# RF_EtherCard_Maniac.net
KiCad netlist of a schematic drawn in EAGLE
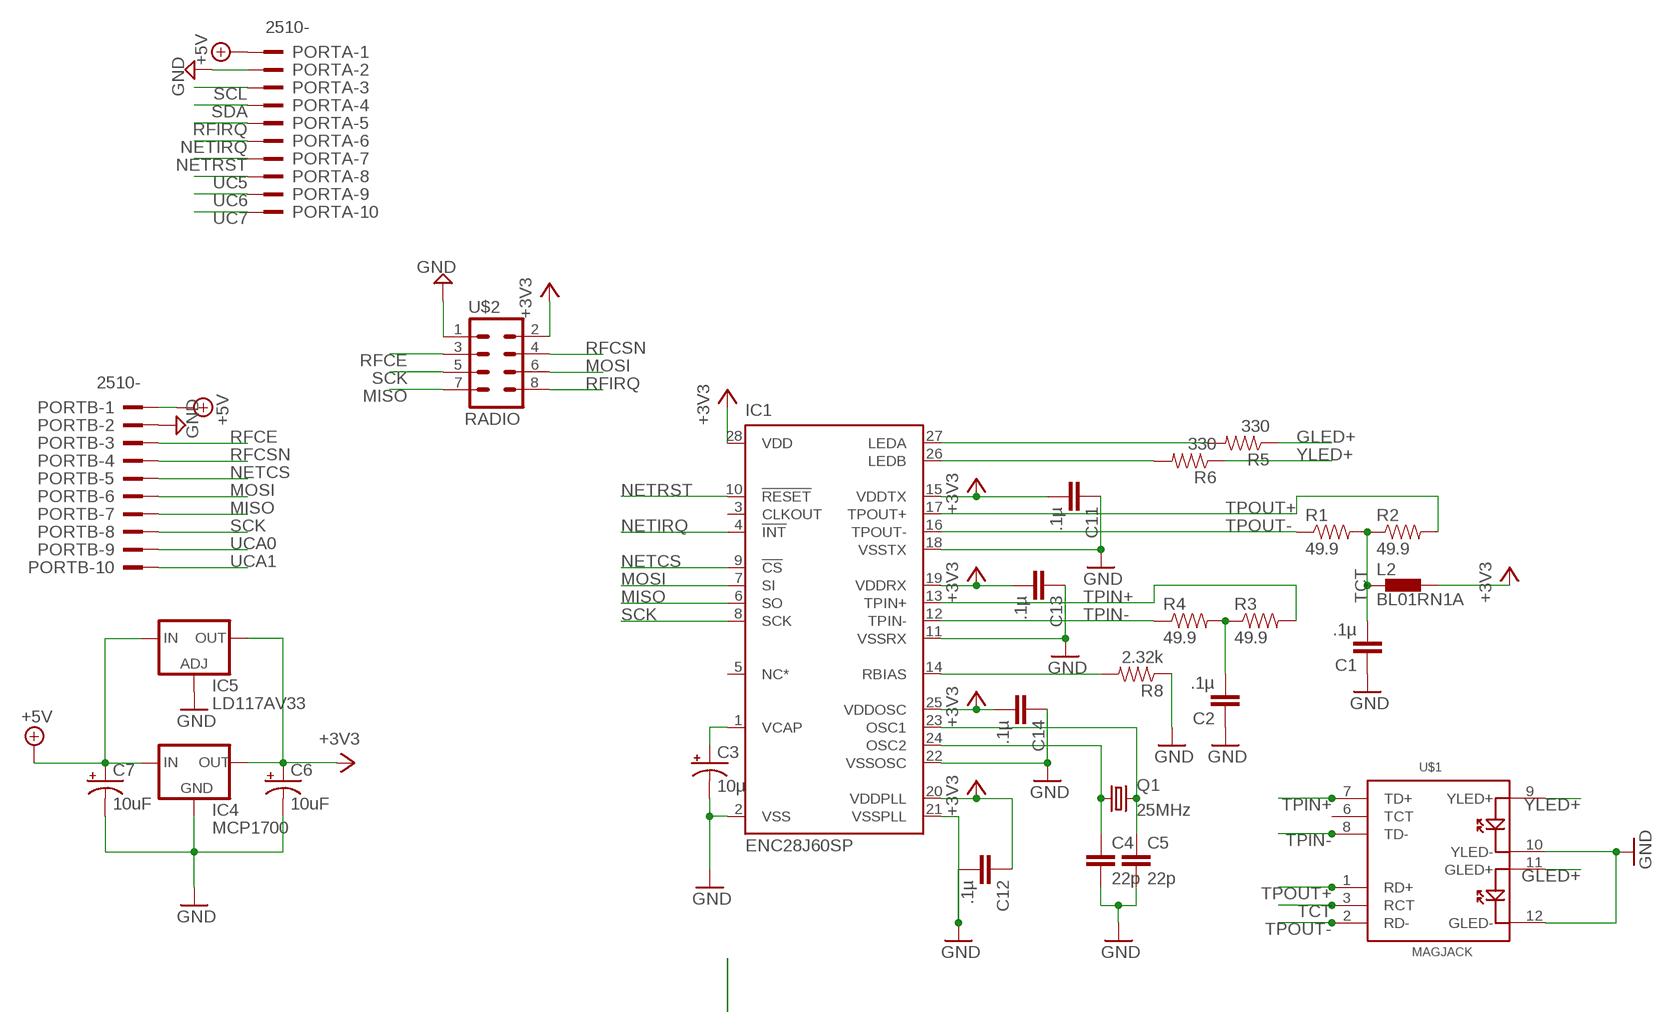
[diagram p0: schematic, sheet 1]

(export (version "E")
  (design (tool "Eeschema 10.0.6"))
  (components
    (comp (ref "C1")
      (value ".1µ")
      (footprint "eagle-import:CAP-PTH-SMALL")
      (libsource (lib "eagle-import") (part "CAPPTH"))
    )
    (comp (ref "C2")
      (value ".1µ")
      (footprint "eagle-import:CAP-PTH-SMALL")
      (libsource (lib "eagle-import") (part "CAPPTH"))
    )
    (comp (ref "C3")
      (value "10µ")
      (footprint "eagle-import:CPOL-RADIAL-10UF-25V")
      (libsource (lib "eagle-import") (part "CAP_POLPTH2"))
    )
    (comp (ref "C4")
      (value "22p")
      (footprint "eagle-import:CAP-PTH-SMALL")
      (libsource (lib "eagle-import") (part "CAPPTH"))
    )
    (comp (ref "C5")
      (value "22p")
      (footprint "eagle-import:CAP-PTH-SMALL")
      (libsource (lib "eagle-import") (part "CAPPTH"))
    )
    (comp (ref "C6")
      (value "10uF")
      (footprint "eagle-import:CPOL-RADIAL-10UF-25V")
      (libsource (lib "eagle-import") (part "CAP_POLPTH2"))
    )
    (comp (ref "C7")
      (value "10uF")
      (footprint "eagle-import:CPOL-RADIAL-10UF-25V")
      (libsource (lib "eagle-import") (part "CAP_POLPTH2"))
    )
    (comp (ref "C11")
      (value ".1µ")
      (footprint "eagle-import:CAP-PTH-SMALL")
      (libsource (lib "eagle-import") (part "CAPPTH"))
    )
    (comp (ref "C12")
      (value ".1µ")
      (footprint "eagle-import:CAP-PTH-SMALL")
      (libsource (lib "eagle-import") (part "CAPPTH"))
    )
    (comp (ref "C13")
      (value ".1µ")
      (footprint "eagle-import:CAP-PTH-SMALL")
      (libsource (lib "eagle-import") (part "CAPPTH"))
    )
    (comp (ref "C14")
      (value ".1µ")
      (footprint "eagle-import:CAP-PTH-SMALL")
      (libsource (lib "eagle-import") (part "CAPPTH"))
    )
    (comp (ref "IC1")
      (value "ENC28J60SP")
      (footprint "eagle-import:DIL28-3")
      (libsource (lib "eagle-import") (part "ENC28J60SP"))
    )
    (comp (ref "IC4")
      (value "MCP1700")
      (footprint "eagle-import:TO92A")
      (libsource (lib "eagle-import") (part "MCP1700"))
    )
    (comp (ref "IC5")
      (value "LD117AV33")
      (footprint "eagle-import:TO220L1")
      (libsource (lib "eagle-import") (part "LD117A?V33"))
    )
    (comp (ref "L2")
      (value "BL01RN1A")
      (footprint "eagle-import:BL01RN1A")
      (libsource (lib "eagle-import") (part "BL01RN1A"))
    )
    (comp (ref "PORTA")
      (value "2510-")
      (footprint "eagle-import:PAK100_2500-10")
      (fields (field (name "MF") "3M") (field (name "MPN") "2510-6002UB"))
      (libsource (lib "eagle-import") (part "2510-"))
    )
    (comp (ref "PORTB")
      (value "2510-")
      (footprint "eagle-import:PAK100_2500-10")
      (fields (field (name "MF") "3M") (field (name "MPN") "2510-6002UB"))
      (libsource (lib "eagle-import") (part "2510-"))
    )
    (comp (ref "Q1")
      (value "25MHz")
      (footprint "eagle-import:HC49US")
      (libsource (lib "eagle-import") (part "CRYSTALHC49US"))
    )
    (comp (ref "R1")
      (value "49.9")
      (footprint "eagle-import:AXIAL-0.3")
      (libsource (lib "eagle-import") (part "RESISTORPTH1"))
    )
    (comp (ref "R2")
      (value "49.9")
      (footprint "eagle-import:AXIAL-0.3")
      (libsource (lib "eagle-import") (part "RESISTORPTH1"))
    )
    (comp (ref "R3")
      (value "49.9")
      (footprint "eagle-import:AXIAL-0.3")
      (libsource (lib "eagle-import") (part "RESISTORPTH1"))
    )
    (comp (ref "R4")
      (value "49.9")
      (footprint "eagle-import:AXIAL-0.3")
      (libsource (lib "eagle-import") (part "RESISTORPTH1"))
    )
    (comp (ref "R5")
      (value "330")
      (footprint "eagle-import:AXIAL-0.3")
      (libsource (lib "eagle-import") (part "RESISTORPTH1"))
    )
    (comp (ref "R6")
      (value "330")
      (footprint "eagle-import:AXIAL-0.3")
      (libsource (lib "eagle-import") (part "RESISTORPTH1"))
    )
    (comp (ref "R8")
      (value "2.32k")
      (footprint "eagle-import:AXIAL-0.3")
      (libsource (lib "eagle-import") (part "RESISTORPTH1"))
    )
    (comp (ref "U$1")
      (value "MAGJACK")
      (footprint "eagle-import:MAGJACK")
      (libsource (lib "eagle-import") (part "MAGJACK"))
    )
    (comp (ref "U$2")
      (value "RADIO")
      (footprint "eagle-import:2X4")
      (libsource (lib "eagle-import") (part "M04X2"))
    )
  )
  (nets
    (net (code "1") (name "+3V3") (class "Default")
      (node (ref "C11") (pin "2") (pinfunction "2_2") (pintype "passive"))
      (node (ref "C12") (pin "1") (pinfunction "1_1") (pintype "passive"))
      (node (ref "C13") (pin "2") (pinfunction "2_2") (pintype "passive"))
      (node (ref "C14") (pin "2") (pinfunction "2_2") (pintype "passive"))
      (node (ref "C6") (pin "1") (pinfunction "+_1") (pintype "passive"))
      (node (ref "IC1") (pin "15") (pinfunction "VDDTX_15") (pintype "input"))
      (node (ref "IC1") (pin "19") (pinfunction "VDDRX_19") (pintype "input"))
      (node (ref "IC1") (pin "20") (pinfunction "VDDPLL_20") (pintype "input"))
      (node (ref "IC1") (pin "25") (pinfunction "VDDOSC_25") (pintype "input"))
      (node (ref "IC1") (pin "28") (pinfunction "VDD_28") (pintype "input"))
      (node (ref "IC4") (pin "3") (pinfunction "OUT_3") (pintype "passive"))
      (node (ref "IC5") (pin "2") (pinfunction "OUT_2") (pintype "passive"))
      (node (ref "L2") (pin "2") (pinfunction "2_2") (pintype "passive"))
      (node (ref "U$2") (pin "2") (pinfunction "2_2") (pintype "passive"))
    )
    (net (code "2") (name "+5V") (class "Default")
      (node (ref "C7") (pin "1") (pinfunction "+_1") (pintype "passive"))
      (node (ref "IC4") (pin "2") (pinfunction "IN_2") (pintype "input"))
      (node (ref "IC5") (pin "3") (pinfunction "IN_3") (pintype "input"))
      (node (ref "PORTA") (pin "1") (pinfunction "KL_1") (pintype "passive"))
      (node (ref "PORTB") (pin "1") (pinfunction "KL_1") (pintype "passive"))
    )
    (net (code "3") (name "/GLED+") (class "Default")
      (node (ref "R5") (pin "P$1") (pinfunction "1_P$1") (pintype "passive"))
      (node (ref "U$1") (pin "11") (pinfunction "GLED+_11") (pintype "bidirectional"))
    )
    (net (code "4") (name "/MISO") (class "Default")
      (node (ref "IC1") (pin "6") (pinfunction "SO_6") (pintype "output"))
      (node (ref "PORTB") (pin "7") (pinfunction "KL_7") (pintype "passive"))
      (node (ref "U$2") (pin "7") (pinfunction "7_7") (pintype "passive"))
    )
    (net (code "5") (name "/MOSI") (class "Default")
      (node (ref "IC1") (pin "7") (pinfunction "SI_7") (pintype "input"))
      (node (ref "PORTB") (pin "6") (pinfunction "KL_6") (pintype "passive"))
      (node (ref "U$2") (pin "6") (pinfunction "6_6") (pintype "passive"))
    )
    (net (code "6") (name "/NETCS") (class "Default")
      (node (ref "IC1") (pin "9") (pinfunction "~{CS}_9") (pintype "input"))
      (node (ref "PORTB") (pin "5") (pinfunction "KL_5") (pintype "passive"))
    )
    (net (code "7") (name "/NETIRQ") (class "Default")
      (node (ref "IC1") (pin "4") (pinfunction "~{INT}_4") (pintype "output"))
      (node (ref "PORTA") (pin "6") (pinfunction "KL_6") (pintype "passive"))
    )
    (net (code "8") (name "/NETRST") (class "Default")
      (node (ref "IC1") (pin "10") (pinfunction "~{RESET}_10") (pintype "input"))
      (node (ref "PORTA") (pin "7") (pinfunction "KL_7") (pintype "passive"))
    )
    (net (code "9") (name "/RFCE") (class "Default")
      (node (ref "PORTB") (pin "3") (pinfunction "KL_3") (pintype "passive"))
      (node (ref "U$2") (pin "3") (pinfunction "3_3") (pintype "passive"))
    )
    (net (code "10") (name "/RFCSN") (class "Default")
      (node (ref "PORTB") (pin "4") (pinfunction "KL_4") (pintype "passive"))
      (node (ref "U$2") (pin "4") (pinfunction "4_4") (pintype "passive"))
    )
    (net (code "11") (name "/RFIRQ") (class "Default")
      (node (ref "PORTA") (pin "5") (pinfunction "KL_5") (pintype "passive"))
      (node (ref "U$2") (pin "8") (pinfunction "8_8") (pintype "passive"))
    )
    (net (code "12") (name "/SCK") (class "Default")
      (node (ref "IC1") (pin "8") (pinfunction "SCK_8") (pintype "input"))
      (node (ref "PORTB") (pin "8") (pinfunction "KL_8") (pintype "passive"))
      (node (ref "U$2") (pin "5") (pinfunction "5_5") (pintype "passive"))
    )
    (net (code "13") (name "/SCL") (class "Default")
      (node (ref "PORTA") (pin "3") (pinfunction "KL_3") (pintype "passive"))
    )
    (net (code "14") (name "/SDA") (class "Default")
      (node (ref "PORTA") (pin "4") (pinfunction "KL_4") (pintype "passive"))
    )
    (net (code "15") (name "/TCT") (class "Default")
      (node (ref "C1") (pin "2") (pinfunction "2_2") (pintype "passive"))
      (node (ref "L2") (pin "1") (pinfunction "1_1") (pintype "passive"))
      (node (ref "R1") (pin "P$2") (pinfunction "2_P$2") (pintype "passive"))
      (node (ref "R2") (pin "P$1") (pinfunction "1_P$1") (pintype "passive"))
      (node (ref "U$1") (pin "3") (pinfunction "RCT_3") (pintype "bidirectional"))
    )
    (net (code "16") (name "/TPIN+") (class "Default")
      (node (ref "IC1") (pin "13") (pinfunction "TPIN+_13") (pintype "input"))
      (node (ref "R3") (pin "P$2") (pinfunction "2_P$2") (pintype "passive"))
      (node (ref "U$1") (pin "7") (pinfunction "TD+_7") (pintype "bidirectional"))
    )
    (net (code "17") (name "/TPIN-") (class "Default")
      (node (ref "IC1") (pin "12") (pinfunction "TPIN-_12") (pintype "input"))
      (node (ref "R4") (pin "P$1") (pinfunction "1_P$1") (pintype "passive"))
      (node (ref "U$1") (pin "8") (pinfunction "TD-_8") (pintype "bidirectional"))
    )
    (net (code "18") (name "/TPOUT+") (class "Default")
      (node (ref "IC1") (pin "17") (pinfunction "TPOUT+_17") (pintype "output"))
      (node (ref "R2") (pin "P$2") (pinfunction "2_P$2") (pintype "passive"))
      (node (ref "U$1") (pin "1") (pinfunction "RD+_1") (pintype "bidirectional"))
    )
    (net (code "19") (name "/TPOUT-") (class "Default")
      (node (ref "IC1") (pin "16") (pinfunction "TPOUT-_16") (pintype "output"))
      (node (ref "R1") (pin "P$1") (pinfunction "1_P$1") (pintype "passive"))
      (node (ref "U$1") (pin "2") (pinfunction "RD-_2") (pintype "bidirectional"))
    )
    (net (code "20") (name "/UC5") (class "Default")
      (node (ref "PORTA") (pin "8") (pinfunction "KL_8") (pintype "passive"))
    )
    (net (code "21") (name "/UC6") (class "Default")
      (node (ref "PORTA") (pin "9") (pinfunction "KL_9") (pintype "passive"))
    )
    (net (code "22") (name "/UC7") (class "Default")
      (node (ref "PORTA") (pin "10") (pinfunction "KL_10") (pintype "passive"))
    )
    (net (code "23") (name "/UCA0") (class "Default")
      (node (ref "PORTB") (pin "9") (pinfunction "KL_9") (pintype "passive"))
    )
    (net (code "24") (name "/UCA1") (class "Default")
      (node (ref "PORTB") (pin "10") (pinfunction "KL_10") (pintype "passive"))
    )
    (net (code "25") (name "/YLED+") (class "Default")
      (node (ref "R6") (pin "P$1") (pinfunction "1_P$1") (pintype "passive"))
      (node (ref "U$1") (pin "9") (pinfunction "YLED+_9") (pintype "bidirectional"))
    )
    (net (code "26") (name "GND") (class "Default")
      (node (ref "C1") (pin "1") (pinfunction "1_1") (pintype "passive"))
      (node (ref "C11") (pin "1") (pinfunction "1_1") (pintype "passive"))
      (node (ref "C12") (pin "2") (pinfunction "2_2") (pintype "passive"))
      (node (ref "C13") (pin "1") (pinfunction "1_1") (pintype "passive"))
      (node (ref "C14") (pin "1") (pinfunction "1_1") (pintype "passive"))
      (node (ref "C2") (pin "1") (pinfunction "1_1") (pintype "passive"))
      (node (ref "C3") (pin "2") (pinfunction "-_2") (pintype "passive"))
      (node (ref "C4") (pin "2") (pinfunction "2_2") (pintype "passive"))
      (node (ref "C5") (pin "2") (pinfunction "2_2") (pintype "passive"))
      (node (ref "C6") (pin "2") (pinfunction "-_2") (pintype "passive"))
      (node (ref "C7") (pin "2") (pinfunction "-_2") (pintype "passive"))
      (node (ref "IC1") (pin "11") (pinfunction "VSSRX_11") (pintype "input"))
      (node (ref "IC1") (pin "18") (pinfunction "VSSTX_18") (pintype "input"))
      (node (ref "IC1") (pin "2") (pinfunction "VSS_2") (pintype "input"))
      (node (ref "IC1") (pin "21") (pinfunction "VSSPLL_21") (pintype "input"))
      (node (ref "IC1") (pin "22") (pinfunction "VSSOSC_22") (pintype "input"))
      (node (ref "IC4") (pin "1") (pinfunction "GND_1") (pintype "input"))
      (node (ref "IC5") (pin "1") (pinfunction "ADJ_1") (pintype "input"))
      (node (ref "PORTA") (pin "2") (pinfunction "KL_2") (pintype "passive"))
      (node (ref "PORTB") (pin "2") (pinfunction "KL_2") (pintype "passive"))
      (node (ref "R8") (pin "P$1") (pinfunction "1_P$1") (pintype "passive"))
      (node (ref "U$1") (pin "10") (pinfunction "YLED-_10") (pintype "bidirectional"))
      (node (ref "U$1") (pin "12") (pinfunction "GLED-_12") (pintype "bidirectional"))
      (node (ref "U$2") (pin "1") (pinfunction "1_1") (pintype "passive"))
    )
    (net (code "27") (name "Net-(C3-+)") (class "Default")
      (node (ref "C3") (pin "1") (pinfunction "+_1") (pintype "passive"))
      (node (ref "IC1") (pin "1") (pinfunction "VCAP_1") (pintype "input"))
    )
    (net (code "28") (name "Net-(IC1-LEDA)") (class "Default")
      (node (ref "IC1") (pin "27") (pinfunction "LEDA_27") (pintype "output"))
      (node (ref "R5") (pin "P$2") (pinfunction "2_P$2") (pintype "passive"))
    )
    (net (code "29") (name "Net-(IC1-LEDB)") (class "Default")
      (node (ref "IC1") (pin "26") (pinfunction "LEDB_26") (pintype "output"))
      (node (ref "R6") (pin "P$2") (pinfunction "2_P$2") (pintype "passive"))
    )
    (net (code "30") (name "Net-(IC1-OSC1)") (class "Default")
      (node (ref "C5") (pin "1") (pinfunction "1_1") (pintype "passive"))
      (node (ref "IC1") (pin "23") (pinfunction "OSC1_23") (pintype "input"))
      (node (ref "Q1") (pin "2") (pinfunction "2_2") (pintype "passive"))
    )
    (net (code "31") (name "Net-(IC1-OSC2)") (class "Default")
      (node (ref "C4") (pin "1") (pinfunction "1_1") (pintype "passive"))
      (node (ref "IC1") (pin "24") (pinfunction "OSC2_24") (pintype "output"))
      (node (ref "Q1") (pin "1") (pinfunction "1_1") (pintype "passive"))
    )
    (net (code "32") (name "Net-(IC1-RBIAS)") (class "Default")
      (node (ref "IC1") (pin "14") (pinfunction "RBIAS_14") (pintype "input"))
      (node (ref "R8") (pin "P$2") (pinfunction "2_P$2") (pintype "passive"))
    )
    (net (code "33") (name "Net-(R3-1)") (class "Default")
      (node (ref "C2") (pin "2") (pinfunction "2_2") (pintype "passive"))
      (node (ref "R3") (pin "P$1") (pinfunction "1_P$1") (pintype "passive"))
      (node (ref "R4") (pin "P$2") (pinfunction "2_P$2") (pintype "passive"))
    )
    (net (code "34") (name "unconnected-(IC1-CLKOUT-Pad3)") (class "Default")
      (node (ref "IC1") (pin "3") (pinfunction "CLKOUT_3") (pintype "output"))
    )
    (net (code "35") (name "unconnected-(IC1-NC*-Pad5)") (class "Default")
      (node (ref "IC1") (pin "5") (pinfunction "NC*_5") (pintype "output"))
    )
    (net (code "36") (name "unconnected-(U$1-TCT-Pad6)") (class "Default")
      (node (ref "U$1") (pin "6") (pinfunction "TCT_6") (pintype "bidirectional"))
    )
  )
)
